# adb.net
KiCad netlist of a schematic drawn in EAGLE
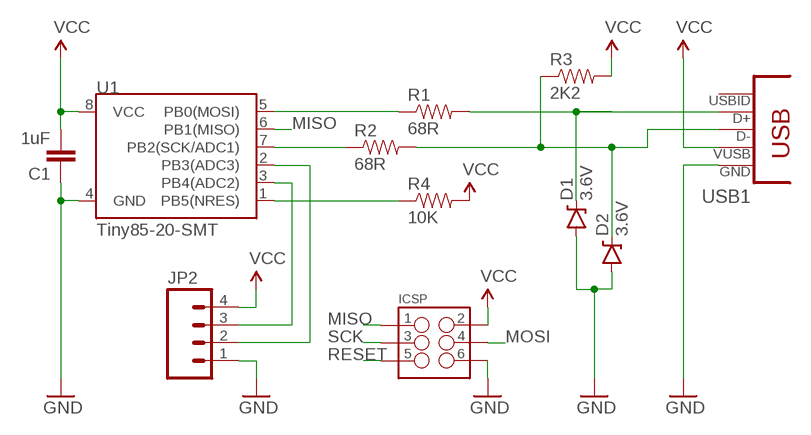
[diagram p0: schematic, sheet 1]

(export (version "E")
  (design (tool "Eeschema 10.0.6"))
  (components
    (comp (ref "C1")
      (value "1uF")
      (footprint "eagle-import:0805")
      (libsource (lib "eagle-import") (part "1.0UF-25V-+80/-20(0805)"))
    )
    (comp (ref "D1")
      (value "3.6V")
      (footprint "eagle-import:SOD-323")
      (libsource (lib "eagle-import") (part "DIODE-ZENER3.3V"))
    )
    (comp (ref "D2")
      (value "3.6V")
      (footprint "eagle-import:SOD-323")
      (libsource (lib "eagle-import") (part "DIODE-ZENER3.3V"))
    )
    (comp (ref "ICSP")
      (value "M03X22X3_SILK_SM")
      (footprint "eagle-import:2X3")
      (libsource (lib "eagle-import") (part "M03X22X3_SILK_SM"))
    )
    (comp (ref "JP2")
      (value "M04PTH")
      (footprint "eagle-import:1X04")
      (libsource (lib "eagle-import") (part "M04PTH"))
    )
    (comp (ref "R1")
      (value "68R")
      (footprint "eagle-import:0805")
      (libsource (lib "eagle-import") (part "RESISTOR0805-RES"))
    )
    (comp (ref "R2")
      (value "68R")
      (footprint "eagle-import:0805")
      (libsource (lib "eagle-import") (part "RESISTOR0805-RES"))
    )
    (comp (ref "R3")
      (value "2K2")
      (footprint "eagle-import:0805")
      (libsource (lib "eagle-import") (part "RESISTOR0805-RES"))
    )
    (comp (ref "R4")
      (value "10K")
      (footprint "eagle-import:0805")
      (libsource (lib "eagle-import") (part "RESISTOR0805-RES"))
    )
    (comp (ref "U1")
      (value "Tiny85-20-SMT")
      (footprint "eagle-import:SO08-EIAJ")
      (libsource (lib "eagle-import") (part "ATTINY45TINY85-20-SMT"))
    )
    (comp (ref "USB1")
      (value "CON-USB-F-MICRO-B")
      (footprint "eagle-import:CONN_USB_MICRO-B")
      (libsource (lib "eagle-import") (part "CON-USB-F-MICRO-B"))
    )
  )
  (nets
    (net (code "1") (name "/MISO") (class "Default")
      (node (ref "ICSP") (pin "1") (pinfunction "1_1") (pintype "bidirectional"))
      (node (ref "U1") (pin "6") (pinfunction "PB1(MISO)_6") (pintype "bidirectional"))
    )
    (net (code "2") (name "/MOSI") (class "Default")
      (node (ref "ICSP") (pin "4") (pinfunction "4_4") (pintype "bidirectional"))
      (node (ref "R1") (pin "1") (pinfunction "1_1") (pintype "passive"))
      (node (ref "U1") (pin "5") (pinfunction "PB0(MOSI)_5") (pintype "bidirectional"))
    )
    (net (code "3") (name "/RESET") (class "Default")
      (node (ref "ICSP") (pin "5") (pinfunction "5_5") (pintype "bidirectional"))
      (node (ref "R4") (pin "1") (pinfunction "1_1") (pintype "passive"))
      (node (ref "U1") (pin "1") (pinfunction "PB5(NRES)_1") (pintype "bidirectional"))
    )
    (net (code "4") (name "/SCK") (class "Default")
      (node (ref "ICSP") (pin "3") (pinfunction "3_3") (pintype "bidirectional"))
      (node (ref "R2") (pin "1") (pinfunction "1_1") (pintype "passive"))
      (node (ref "U1") (pin "7") (pinfunction "PB2(SCK/ADC1)_7") (pintype "bidirectional"))
    )
    (net (code "5") (name "GND") (class "Default")
      (node (ref "C1") (pin "1") (pinfunction "1_1") (pintype "passive"))
      (node (ref "D1") (pin "A") (pinfunction "A_A") (pintype "passive"))
      (node (ref "D2") (pin "A") (pinfunction "A_A") (pintype "passive"))
      (node (ref "ICSP") (pin "6") (pinfunction "6_6") (pintype "bidirectional"))
      (node (ref "JP2") (pin "1") (pinfunction "1_1") (pintype "passive"))
      (node (ref "U1") (pin "4") (pinfunction "GND_4") (pintype "bidirectional"))
      (node (ref "USB1") (pin "P5") (pinfunction "GND_P5") (pintype "bidirectional"))
    )
    (net (code "6") (name "Net-(U1-PB3(ADC3))") (class "Default")
      (node (ref "JP2") (pin "2") (pinfunction "2_2") (pintype "passive"))
      (node (ref "U1") (pin "2") (pinfunction "PB3(ADC3)_2") (pintype "bidirectional"))
    )
    (net (code "7") (name "Net-(U1-PB4(ADC2))") (class "Default")
      (node (ref "JP2") (pin "3") (pinfunction "3_3") (pintype "passive"))
      (node (ref "U1") (pin "3") (pinfunction "PB4(ADC2)_3") (pintype "bidirectional"))
    )
    (net (code "8") (name "Net-(USB1B-D+)") (class "Default")
      (node (ref "D1") (pin "C") (pinfunction "C_C") (pintype "passive"))
      (node (ref "R1") (pin "2") (pinfunction "2_2") (pintype "passive"))
      (node (ref "USB1") (pin "P3") (pinfunction "D+_P3") (pintype "bidirectional"))
    )
    (net (code "9") (name "Net-(USB1B-D-)") (class "Default")
      (node (ref "D2") (pin "C") (pinfunction "C_C") (pintype "passive"))
      (node (ref "R2") (pin "2") (pinfunction "2_2") (pintype "passive"))
      (node (ref "R3") (pin "1") (pinfunction "1_1") (pintype "passive"))
      (node (ref "USB1") (pin "P2") (pinfunction "D-_P2") (pintype "bidirectional"))
    )
    (net (code "10") (name "VCC") (class "Default")
      (node (ref "C1") (pin "2") (pinfunction "2_2") (pintype "passive"))
      (node (ref "ICSP") (pin "2") (pinfunction "2_2") (pintype "bidirectional"))
      (node (ref "JP2") (pin "4") (pinfunction "4_4") (pintype "passive"))
      (node (ref "R3") (pin "2") (pinfunction "2_2") (pintype "passive"))
      (node (ref "R4") (pin "2") (pinfunction "2_2") (pintype "passive"))
      (node (ref "U1") (pin "8") (pinfunction "VCC_8") (pintype "bidirectional"))
      (node (ref "USB1") (pin "P1") (pinfunction "VUSB_P1") (pintype "bidirectional"))
    )
    (net (code "11") (name "unconnected-(USB1B-USBID-PadP4)") (class "Default")
      (node (ref "USB1") (pin "P4") (pinfunction "USBID_P4") (pintype "bidirectional"))
    )
  )
)
